# ArduinoUnoShield.net
KiCad netlist of a schematic drawn in Altium Designer
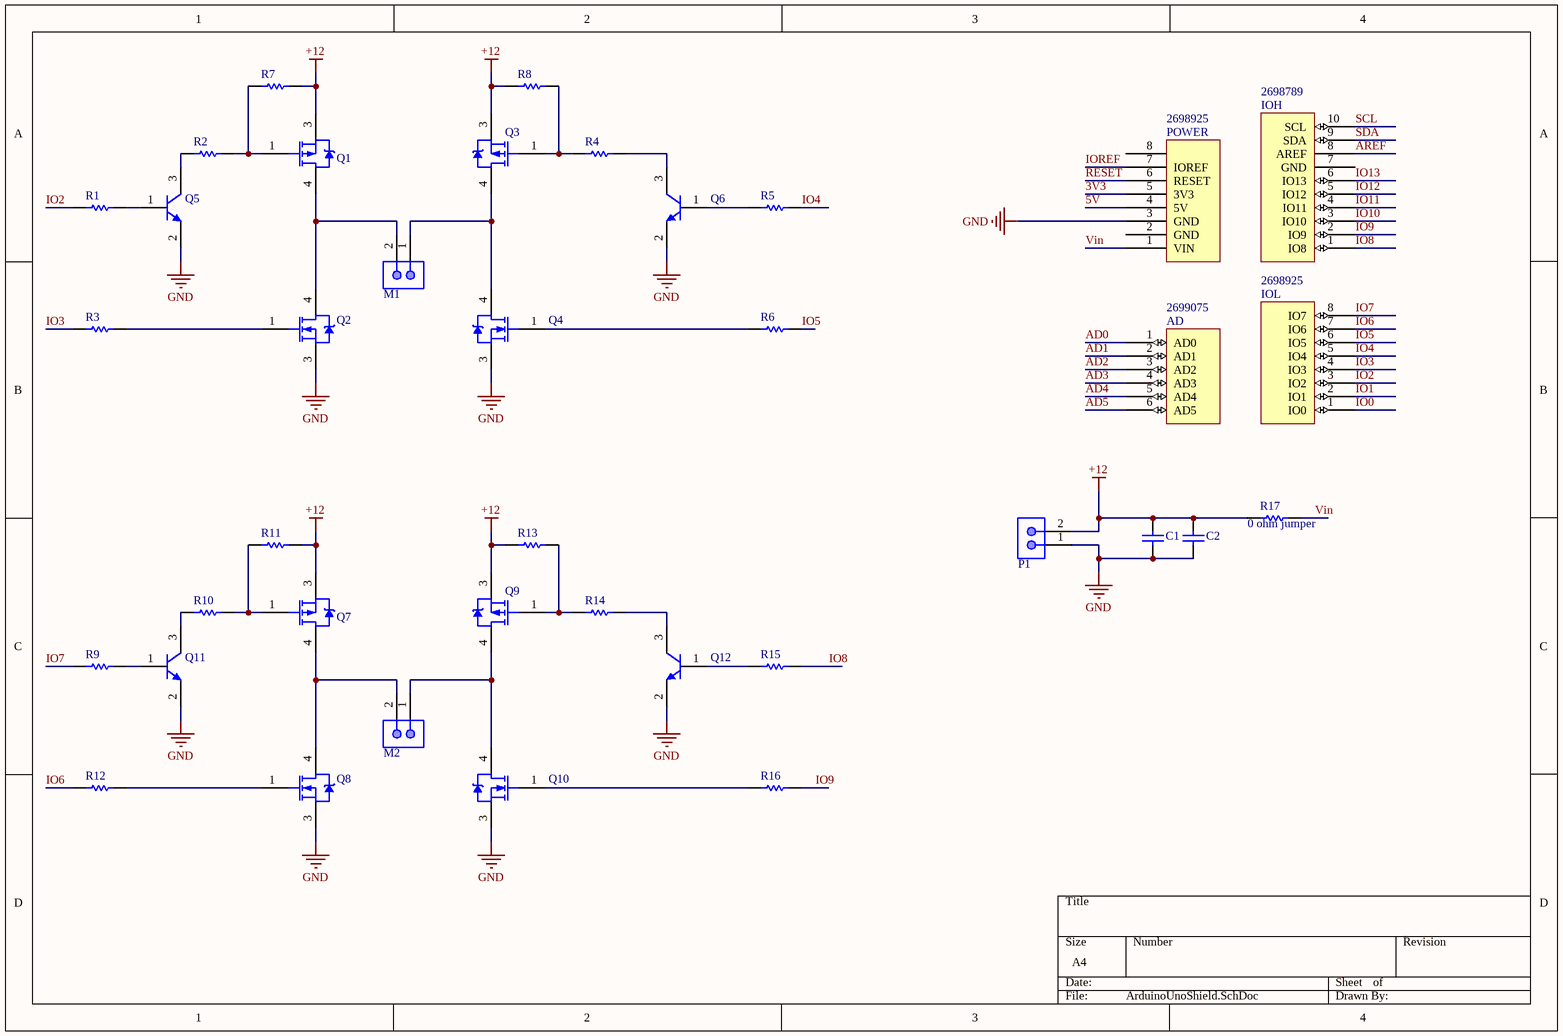
[diagram p0: ArduinoUnoShield.SchDoc]

(export (version "E")
  (design (tool "Eeschema 10.0.6"))
  (components
    (comp (ref "AD")
      (value "AD")
      (footprint "Header:Header 6x1 8.5mm")
      (fields (field (name "SUPPLIER PART NUMBER 4") "2699075"))
      (libsource (lib "Header") (part "AD"))
    )
    (comp (ref "C1")
      (value "CAP 100nF 50V 1206(3216)")
      (footprint "CAPC1206(3216)100_L")
      (description "CAP 100nF 50V ±10% 1206 (3216 Metric) Thickness 1mm SMD")
      (fields (field (name "TOLERANCE") "Â±10%"))
      (libsource (lib "Altium Content Vault") (part "CAP"))
    )
    (comp (ref "C2")
      (value "CAP 100nF 50V 1206(3216)")
      (footprint "CAPC1206(3216)100_L")
      (description "CAP 100nF 50V ±10% 1206 (3216 Metric) Thickness 1mm SMD")
      (fields (field (name "TOLERANCE") "Â±10%"))
      (libsource (lib "Altium Content Vault") (part "CAP"))
    )
    (comp (ref "IOH")
      (value "IOH")
      (footprint "Header:Header 10x1 8.5mm")
      (fields (field (name "SUPPLIER PART NUMBER 3") "2698789"))
      (libsource (lib "Header") (part "IOH"))
    )
    (comp (ref "IOL")
      (value "IOL")
      (footprint "Header 8x1 8.5mm")
      (fields (field (name "SUPPLIER PART NUMBER 4") "2698925"))
      (libsource (lib "Header") (part "IOL"))
    )
    (comp (ref "M1")
      (value "68000-102HLF")
      (footprint "AMPH-68000-102HLF_V")
      (description "Male Header, Pitch 2.54 mm, 1 x 2 Position, Height 8.38 mm, Tail Length 2.41 mm, RoHS, Bulk")
      (fields (field (name "MANUFACTURER") "FCI"))
      (libsource (lib "Altium Content Vault") (part "CN-1P-M-R2"))
    )
    (comp (ref "M2")
      (value "68000-102HLF")
      (footprint "AMPH-68000-102HLF_V")
      (description "Male Header, Pitch 2.54 mm, 1 x 2 Position, Height 8.38 mm, Tail Length 2.41 mm, RoHS, Bulk")
      (fields (field (name "MANUFACTURER") "FCI"))
      (libsource (lib "Altium Content Vault") (part "CN-1P-M-R2"))
    )
    (comp (ref "P1")
      (value "68000-102HLF")
      (footprint "AMPH-68000-102HLF_V")
      (description "Male Header, Pitch 2.54 mm, 1 x 2 Position, Height 8.38 mm, Tail Length 2.41 mm, RoHS, Bulk")
      (fields (field (name "MANUFACTURER") "FCI"))
      (libsource (lib "") (part "CN-1P-M-R2_1"))
    )
    (comp (ref "POWER")
      (value "POWER_UNO")
      (footprint "Header 8x1 8.5mm")
      (fields (field (name "SUPPLIER PART NUMBER 4") "2698925"))
      (libsource (lib "Header") (part "POWER_UNO"))
    )
    (comp (ref "Q1")
      (value "IRF9630STRLPBF‎")
      (footprint "ONSC-D2PAK-3-418B-04_V")
      (description "Power MOSFET, 50 A, 30 V, Logic Level, P-Channel, 3-Pin D2PAK, Pb-Free, Tape and Reel")
      (fields (field (name "PARTNUMBER") "MTB50P03HDLT4G") (field (name "MANUFACTURER") "On Semiconductor"))
      (libsource (lib "Altium Content Vault") (part "ONSC-PMOS-G1S3D4-3_B"))
    )
    (comp (ref "Q2")
      (value "IRF630NSTRLPBF‎")
      (footprint "ONSC-D2PAK-3-418B-04_V")
      (description "Power MOSFET, 60 V, 60 A, N-Channel, 3-Pin D2PAK, Pb-Free, Tape and Reel")
      (fields (field (name "MANUFACTURER") "On Semiconductor") (field (name "PARTNUMBER") "NTB60N06T4G"))
      (libsource (lib "Altium Content Vault") (part "ONSC-NMOS-G1S3D4-3_C"))
    )
    (comp (ref "Q3")
      (value "IRF9630STRLPBF‎")
      (footprint "ONSC-D2PAK-3-418B-04_V")
      (description "Power MOSFET, 50 A, 30 V, Logic Level, P-Channel, 3-Pin D2PAK, Pb-Free, Tape and Reel")
      (fields (field (name "PARTNUMBER") "MTB50P03HDLT4G") (field (name "MANUFACTURER") "On Semiconductor"))
      (libsource (lib "Altium Content Vault") (part "ONSC-PMOS-G1S3D4-3_B"))
    )
    (comp (ref "Q4")
      (value "IRF630NSTRLPBF‎")
      (footprint "ONSC-D2PAK-3-418B-04_V")
      (description "Power MOSFET, 60 V, 60 A, N-Channel, 3-Pin D2PAK, Pb-Free, Tape and Reel")
      (fields (field (name "MANUFACTURER") "On Semiconductor") (field (name "PARTNUMBER") "NTB60N06T4G"))
      (libsource (lib "Altium Content Vault") (part "ONSC-NMOS-G1S3D4-3_C"))
    )
    (comp (ref "Q5")
      (value "BC817-16LT1G")
      (footprint "ONSC-SOT-23-3-318-08_V")
      (description "General Purpose Transistor, NPN Silicon, 3-Pin SOT-23, Pb-Free, Tape and Reel")
      (fields (field (name "MANUFACTURER") "On Semiconductor"))
      (libsource (lib "Altium Content Vault") (part "ONSC-NPN-B1E2C3-3"))
    )
    (comp (ref "Q6")
      (value "BC817-16LT1G")
      (footprint "ONSC-SOT-23-3-318-08_V")
      (description "General Purpose Transistor, NPN Silicon, 3-Pin SOT-23, Pb-Free, Tape and Reel")
      (fields (field (name "MANUFACTURER") "On Semiconductor"))
      (libsource (lib "Altium Content Vault") (part "ONSC-NPN-B1E2C3-3"))
    )
    (comp (ref "Q7")
      (value "IRF9630STRLPBF‎")
      (footprint "ONSC-D2PAK-3-418B-04_V")
      (description "Power MOSFET, 50 A, 30 V, Logic Level, P-Channel, 3-Pin D2PAK, Pb-Free, Tape and Reel")
      (fields (field (name "PARTNUMBER") "MTB50P03HDLT4G") (field (name "MANUFACTURER") "On Semiconductor"))
      (libsource (lib "Altium Content Vault") (part "ONSC-PMOS-G1S3D4-3_B"))
    )
    (comp (ref "Q8")
      (value "IRF630NSTRLPBF‎")
      (footprint "ONSC-D2PAK-3-418B-04_V")
      (description "Power MOSFET, 60 V, 60 A, N-Channel, 3-Pin D2PAK, Pb-Free, Tape and Reel")
      (fields (field (name "MANUFACTURER") "On Semiconductor") (field (name "PARTNUMBER") "NTB60N06T4G"))
      (libsource (lib "Altium Content Vault") (part "ONSC-NMOS-G1S3D4-3_C"))
    )
    (comp (ref "Q9")
      (value "IRF9630STRLPBF‎")
      (footprint "ONSC-D2PAK-3-418B-04_V")
      (description "Power MOSFET, 50 A, 30 V, Logic Level, P-Channel, 3-Pin D2PAK, Pb-Free, Tape and Reel")
      (fields (field (name "PARTNUMBER") "MTB50P03HDLT4G") (field (name "MANUFACTURER") "On Semiconductor"))
      (libsource (lib "Altium Content Vault") (part "ONSC-PMOS-G1S3D4-3_B"))
    )
    (comp (ref "Q10")
      (value "IRF630NSTRLPBF‎")
      (footprint "ONSC-D2PAK-3-418B-04_V")
      (description "Power MOSFET, 60 V, 60 A, N-Channel, 3-Pin D2PAK, Pb-Free, Tape and Reel")
      (fields (field (name "MANUFACTURER") "On Semiconductor") (field (name "PARTNUMBER") "NTB60N06T4G"))
      (libsource (lib "Altium Content Vault") (part "ONSC-NMOS-G1S3D4-3_C"))
    )
    (comp (ref "Q11")
      (value "BC817-16LT1G")
      (footprint "ONSC-SOT-23-3-318-08_V")
      (description "General Purpose Transistor, NPN Silicon, 3-Pin SOT-23, Pb-Free, Tape and Reel")
      (fields (field (name "MANUFACTURER") "On Semiconductor"))
      (libsource (lib "Altium Content Vault") (part "ONSC-NPN-B1E2C3-3"))
    )
    (comp (ref "Q12")
      (value "BC817-16LT1G")
      (footprint "ONSC-SOT-23-3-318-08_V")
      (description "General Purpose Transistor, NPN Silicon, 3-Pin SOT-23, Pb-Free, Tape and Reel")
      (fields (field (name "MANUFACTURER") "On Semiconductor"))
      (libsource (lib "Altium Content Vault") (part "ONSC-NPN-B1E2C3-3"))
    )
    (comp (ref "R1")
      (value "CRCW1206220KFKEA")
      (footprint "RESC3216X60X45NL10T20")
      (fields (field (name "MANUFACTURER") "Vishay Dale"))
      (libsource (lib "Altium Content Vault") (part "RES"))
    )
    (comp (ref "R2")
      (value "CRCW1206220KFKEA")
      (footprint "RESC3216X60X45NL10T20")
      (fields (field (name "MANUFACTURER") "Vishay Dale"))
      (libsource (lib "Altium Content Vault") (part "RES"))
    )
    (comp (ref "R3")
      (value "CRCW1206220KFKEA")
      (footprint "RESC3216X60X45NL10T20")
      (fields (field (name "MANUFACTURER") "Vishay Dale"))
      (libsource (lib "Altium Content Vault") (part "RES"))
    )
    (comp (ref "R4")
      (value "CRCW1206220KFKEA")
      (footprint "RESC3216X60X45NL10T20")
      (fields (field (name "MANUFACTURER") "Vishay Dale"))
      (libsource (lib "Altium Content Vault") (part "RES"))
    )
    (comp (ref "R5")
      (value "CRCW1206220KFKEA")
      (footprint "RESC3216X60X45NL10T20")
      (fields (field (name "MANUFACTURER") "Vishay Dale"))
      (libsource (lib "Altium Content Vault") (part "RES"))
    )
    (comp (ref "R6")
      (value "CRCW1206220KFKEA")
      (footprint "RESC3216X60X45NL10T20")
      (fields (field (name "MANUFACTURER") "Vishay Dale"))
      (libsource (lib "Altium Content Vault") (part "RES"))
    )
    (comp (ref "R7")
      (value "CRCW1206220KFKEA")
      (footprint "RESC3216X60X45NL10T20")
      (fields (field (name "MANUFACTURER") "Vishay Dale"))
      (libsource (lib "Altium Content Vault") (part "RES"))
    )
    (comp (ref "R8")
      (value "CRCW1206220KFKEA")
      (footprint "RESC3216X60X45NL10T20")
      (fields (field (name "MANUFACTURER") "Vishay Dale"))
      (libsource (lib "Altium Content Vault") (part "RES"))
    )
    (comp (ref "R9")
      (value "CRCW1206220KFKEA")
      (footprint "RESC3216X60X45NL10T20")
      (fields (field (name "MANUFACTURER") "Vishay Dale"))
      (libsource (lib "Altium Content Vault") (part "RES"))
    )
    (comp (ref "R10")
      (value "CRCW1206220KFKEA")
      (footprint "RESC3216X60X45NL10T20")
      (fields (field (name "MANUFACTURER") "Vishay Dale"))
      (libsource (lib "Altium Content Vault") (part "RES"))
    )
    (comp (ref "R11")
      (value "CRCW1206220KFKEA")
      (footprint "RESC3216X60X45NL10T20")
      (fields (field (name "MANUFACTURER") "Vishay Dale"))
      (libsource (lib "Altium Content Vault") (part "RES"))
    )
    (comp (ref "R12")
      (value "CRCW1206220KFKEA")
      (footprint "RESC3216X60X45NL10T20")
      (fields (field (name "MANUFACTURER") "Vishay Dale"))
      (libsource (lib "Altium Content Vault") (part "RES"))
    )
    (comp (ref "R13")
      (value "CRCW1206220KFKEA")
      (footprint "RESC3216X60X45NL10T20")
      (fields (field (name "MANUFACTURER") "Vishay Dale"))
      (libsource (lib "Altium Content Vault") (part "RES"))
    )
    (comp (ref "R14")
      (value "CRCW1206220KFKEA")
      (footprint "RESC3216X60X45NL10T20")
      (fields (field (name "MANUFACTURER") "Vishay Dale"))
      (libsource (lib "Altium Content Vault") (part "RES"))
    )
    (comp (ref "R15")
      (value "CRCW1206220KFKEA")
      (footprint "RESC3216X60X45NL10T20")
      (fields (field (name "MANUFACTURER") "Vishay Dale"))
      (libsource (lib "Altium Content Vault") (part "RES"))
    )
    (comp (ref "R16")
      (value "CRCW1206220KFKEA")
      (footprint "RESC3216X60X45NL10T20")
      (fields (field (name "MANUFACTURER") "Vishay Dale"))
      (libsource (lib "Altium Content Vault") (part "RES"))
    )
    (comp (ref "R17")
      (value "CRCW1206220KFKEA")
      (footprint "RESC3216X60X45NL10T20")
      (fields (field (name "MANUFACTURER") "Vishay Dale"))
      (libsource (lib "Altium Content Vault") (part "RES"))
    )
  )
  (nets
    (net (code "1") (name "+12") (class "Default")
      (node (ref "C1") (pin "1") (pinfunction "1_1") (pintype "passive"))
      (node (ref "C2") (pin "1") (pinfunction "1_1") (pintype "passive"))
      (node (ref "P1") (pin "2") (pinfunction "2_2") (pintype "passive"))
      (node (ref "Q1") (pin "3") (pinfunction "S_3") (pintype "passive"))
      (node (ref "Q3") (pin "3") (pinfunction "S_3") (pintype "passive"))
      (node (ref "Q7") (pin "3") (pinfunction "S_3") (pintype "passive"))
      (node (ref "Q9") (pin "3") (pinfunction "S_3") (pintype "passive"))
      (node (ref "R11") (pin "2") (pinfunction "2_2") (pintype "passive"))
      (node (ref "R13") (pin "1") (pinfunction "1_1") (pintype "passive"))
      (node (ref "R17") (pin "1") (pinfunction "1_1") (pintype "passive"))
      (node (ref "R7") (pin "2") (pinfunction "2_2") (pintype "passive"))
      (node (ref "R8") (pin "1") (pinfunction "1_1") (pintype "passive"))
    )
    (net (code "2") (name "/3V3") (class "Default")
      (node (ref "POWER") (pin "5") (pinfunction "3V3_5") (pintype "power_in"))
    )
    (net (code "3") (name "/5V") (class "Default")
      (node (ref "POWER") (pin "4") (pinfunction "5V_4") (pintype "power_in"))
    )
    (net (code "5") (name "/AD0") (class "Default")
      (node (ref "AD") (pin "1") (pinfunction "AD0_1") (pintype "bidirectional"))
    )
    (net (code "6") (name "/AD1") (class "Default")
      (node (ref "AD") (pin "2") (pinfunction "AD1_2") (pintype "bidirectional"))
    )
    (net (code "7") (name "/AD2") (class "Default")
      (node (ref "AD") (pin "3") (pinfunction "AD2_3") (pintype "bidirectional"))
    )
    (net (code "8") (name "/AD3") (class "Default")
      (node (ref "AD") (pin "4") (pinfunction "AD3_4") (pintype "bidirectional"))
    )
    (net (code "9") (name "/AD4") (class "Default")
      (node (ref "AD") (pin "5") (pinfunction "AD4_5") (pintype "bidirectional"))
    )
    (net (code "10") (name "/AD5") (class "Default")
      (node (ref "AD") (pin "6") (pinfunction "AD5_6") (pintype "bidirectional"))
    )
    (net (code "11") (name "/AREF") (class "Default")
      (node (ref "IOH") (pin "8") (pinfunction "AREF_8") (pintype "passive"))
    )
    (net (code "12") (name "/IO0") (class "Default")
      (node (ref "IOL") (pin "1") (pinfunction "IO0_1") (pintype "bidirectional"))
    )
    (net (code "13") (name "/IO1") (class "Default")
      (node (ref "IOL") (pin "2") (pinfunction "IO1_2") (pintype "bidirectional"))
    )
    (net (code "14") (name "/IO2") (class "Default")
      (node (ref "IOL") (pin "3") (pinfunction "IO2_3") (pintype "bidirectional"))
      (node (ref "R1") (pin "1") (pinfunction "1_1") (pintype "passive"))
    )
    (net (code "15") (name "/IO3") (class "Default")
      (node (ref "IOL") (pin "4") (pinfunction "IO3_4") (pintype "bidirectional"))
      (node (ref "R3") (pin "1") (pinfunction "1_1") (pintype "passive"))
    )
    (net (code "16") (name "/IO4") (class "Default")
      (node (ref "IOL") (pin "5") (pinfunction "IO4_5") (pintype "bidirectional"))
      (node (ref "R5") (pin "2") (pinfunction "2_2") (pintype "passive"))
    )
    (net (code "17") (name "/IO5") (class "Default")
      (node (ref "IOL") (pin "6") (pinfunction "IO5_6") (pintype "bidirectional"))
      (node (ref "R6") (pin "2") (pinfunction "2_2") (pintype "passive"))
    )
    (net (code "18") (name "/IO6") (class "Default")
      (node (ref "IOL") (pin "7") (pinfunction "IO6_7") (pintype "bidirectional"))
      (node (ref "R12") (pin "1") (pinfunction "1_1") (pintype "passive"))
    )
    (net (code "19") (name "/IO7") (class "Default")
      (node (ref "IOL") (pin "8") (pinfunction "IO7_8") (pintype "bidirectional"))
      (node (ref "R9") (pin "1") (pinfunction "1_1") (pintype "passive"))
    )
    (net (code "20") (name "/IO8") (class "Default")
      (node (ref "IOH") (pin "1") (pinfunction "IO8_1") (pintype "bidirectional"))
      (node (ref "R15") (pin "2") (pinfunction "2_2") (pintype "passive"))
    )
    (net (code "21") (name "/IO9") (class "Default")
      (node (ref "IOH") (pin "2") (pinfunction "IO9_2") (pintype "bidirectional"))
      (node (ref "R16") (pin "2") (pinfunction "2_2") (pintype "passive"))
    )
    (net (code "22") (name "/IO10") (class "Default")
      (node (ref "IOH") (pin "3") (pinfunction "IO10_3") (pintype "bidirectional"))
    )
    (net (code "23") (name "/IO11") (class "Default")
      (node (ref "IOH") (pin "4") (pinfunction "IO11_4") (pintype "bidirectional"))
    )
    (net (code "24") (name "/IO12") (class "Default")
      (node (ref "IOH") (pin "5") (pinfunction "IO12_5") (pintype "bidirectional"))
    )
    (net (code "25") (name "/IO13") (class "Default")
      (node (ref "IOH") (pin "6") (pinfunction "IO13_6") (pintype "bidirectional"))
    )
    (net (code "26") (name "/IOREF") (class "Default")
      (node (ref "POWER") (pin "7") (pinfunction "IOREF_7") (pintype "power_in"))
    )
    (net (code "27") (name "/RESET") (class "Default")
      (node (ref "POWER") (pin "6") (pinfunction "RESET_6") (pintype "passive"))
    )
    (net (code "28") (name "/SCL") (class "Default")
      (node (ref "IOH") (pin "10") (pinfunction "SCL_10") (pintype "bidirectional"))
    )
    (net (code "29") (name "/SDA") (class "Default")
      (node (ref "IOH") (pin "9") (pinfunction "SDA_9") (pintype "bidirectional"))
    )
    (net (code "30") (name "/Vin") (class "Default")
      (node (ref "POWER") (pin "1") (pinfunction "VIN_1") (pintype "power_in"))
      (node (ref "R17") (pin "2") (pinfunction "2_2") (pintype "passive"))
    )
    (net (code "31") (name "GND") (class "Default")
      (node (ref "C1") (pin "2") (pinfunction "2_2") (pintype "passive"))
      (node (ref "C2") (pin "2") (pinfunction "2_2") (pintype "passive"))
      (node (ref "P1") (pin "1") (pinfunction "1_1") (pintype "passive"))
      (node (ref "POWER") (pin "3") (pinfunction "GND_3") (pintype "power_in"))
      (node (ref "Q10") (pin "3") (pinfunction "S_3") (pintype "passive"))
      (node (ref "Q11") (pin "2") (pinfunction "E_2") (pintype "passive"))
      (node (ref "Q12") (pin "2") (pinfunction "E_2") (pintype "passive"))
      (node (ref "Q2") (pin "3") (pinfunction "S_3") (pintype "passive"))
      (node (ref "Q4") (pin "3") (pinfunction "S_3") (pintype "passive"))
      (node (ref "Q5") (pin "2") (pinfunction "E_2") (pintype "passive"))
      (node (ref "Q6") (pin "2") (pinfunction "E_2") (pintype "passive"))
      (node (ref "Q8") (pin "3") (pinfunction "S_3") (pintype "passive"))
    )
    (net (code "32") (name "Net-(Q1-D)") (class "Default")
      (node (ref "M1") (pin "2") (pinfunction "2_2") (pintype "passive"))
      (node (ref "Q1") (pin "4") (pinfunction "D_4") (pintype "passive"))
      (node (ref "Q2") (pin "4") (pinfunction "D_4") (pintype "passive"))
    )
    (net (code "33") (name "Net-(Q1-G)") (class "Default")
      (node (ref "Q1") (pin "1") (pinfunction "G_1") (pintype "passive"))
      (node (ref "R2") (pin "2") (pinfunction "2_2") (pintype "passive"))
      (node (ref "R7") (pin "1") (pinfunction "1_1") (pintype "passive"))
    )
    (net (code "34") (name "Net-(Q2-G)") (class "Default")
      (node (ref "Q2") (pin "1") (pinfunction "G_1") (pintype "passive"))
      (node (ref "R3") (pin "2") (pinfunction "2_2") (pintype "passive"))
    )
    (net (code "35") (name "Net-(Q3-D)") (class "Default")
      (node (ref "M1") (pin "1") (pinfunction "1_1") (pintype "passive"))
      (node (ref "Q3") (pin "4") (pinfunction "D_4") (pintype "passive"))
      (node (ref "Q4") (pin "4") (pinfunction "D_4") (pintype "passive"))
    )
    (net (code "36") (name "Net-(Q3-G)") (class "Default")
      (node (ref "Q3") (pin "1") (pinfunction "G_1") (pintype "passive"))
      (node (ref "R4") (pin "1") (pinfunction "1_1") (pintype "passive"))
      (node (ref "R8") (pin "2") (pinfunction "2_2") (pintype "passive"))
    )
    (net (code "37") (name "Net-(Q4-G)") (class "Default")
      (node (ref "Q4") (pin "1") (pinfunction "G_1") (pintype "passive"))
      (node (ref "R6") (pin "1") (pinfunction "1_1") (pintype "passive"))
    )
    (net (code "38") (name "Net-(Q5-B)") (class "Default")
      (node (ref "Q5") (pin "1") (pinfunction "B_1") (pintype "passive"))
      (node (ref "R1") (pin "2") (pinfunction "2_2") (pintype "passive"))
    )
    (net (code "39") (name "Net-(Q5-C)") (class "Default")
      (node (ref "Q5") (pin "3") (pinfunction "C_3") (pintype "passive"))
      (node (ref "R2") (pin "1") (pinfunction "1_1") (pintype "passive"))
    )
    (net (code "40") (name "Net-(Q6-B)") (class "Default")
      (node (ref "Q6") (pin "1") (pinfunction "B_1") (pintype "passive"))
      (node (ref "R5") (pin "1") (pinfunction "1_1") (pintype "passive"))
    )
    (net (code "41") (name "Net-(Q6-C)") (class "Default")
      (node (ref "Q6") (pin "3") (pinfunction "C_3") (pintype "passive"))
      (node (ref "R4") (pin "2") (pinfunction "2_2") (pintype "passive"))
    )
    (net (code "42") (name "Net-(Q7-D)") (class "Default")
      (node (ref "M2") (pin "2") (pinfunction "2_2") (pintype "passive"))
      (node (ref "Q7") (pin "4") (pinfunction "D_4") (pintype "passive"))
      (node (ref "Q8") (pin "4") (pinfunction "D_4") (pintype "passive"))
    )
    (net (code "43") (name "Net-(Q7-G)") (class "Default")
      (node (ref "Q7") (pin "1") (pinfunction "G_1") (pintype "passive"))
      (node (ref "R10") (pin "2") (pinfunction "2_2") (pintype "passive"))
      (node (ref "R11") (pin "1") (pinfunction "1_1") (pintype "passive"))
    )
    (net (code "44") (name "Net-(Q8-G)") (class "Default")
      (node (ref "Q8") (pin "1") (pinfunction "G_1") (pintype "passive"))
      (node (ref "R12") (pin "2") (pinfunction "2_2") (pintype "passive"))
    )
    (net (code "45") (name "Net-(Q9-G)") (class "Default")
      (node (ref "Q9") (pin "1") (pinfunction "G_1") (pintype "passive"))
      (node (ref "R13") (pin "2") (pinfunction "2_2") (pintype "passive"))
      (node (ref "R14") (pin "1") (pinfunction "1_1") (pintype "passive"))
    )
    (net (code "46") (name "Net-(Q10-D)") (class "Default")
      (node (ref "M2") (pin "1") (pinfunction "1_1") (pintype "passive"))
      (node (ref "Q10") (pin "4") (pinfunction "D_4") (pintype "passive"))
      (node (ref "Q9") (pin "4") (pinfunction "D_4") (pintype "passive"))
    )
    (net (code "47") (name "Net-(Q10-G)") (class "Default")
      (node (ref "Q10") (pin "1") (pinfunction "G_1") (pintype "passive"))
      (node (ref "R16") (pin "1") (pinfunction "1_1") (pintype "passive"))
    )
    (net (code "48") (name "Net-(Q11-B)") (class "Default")
      (node (ref "Q11") (pin "1") (pinfunction "B_1") (pintype "passive"))
      (node (ref "R9") (pin "2") (pinfunction "2_2") (pintype "passive"))
    )
    (net (code "49") (name "Net-(Q11-C)") (class "Default")
      (node (ref "Q11") (pin "3") (pinfunction "C_3") (pintype "passive"))
      (node (ref "R10") (pin "1") (pinfunction "1_1") (pintype "passive"))
    )
    (net (code "50") (name "Net-(Q12-B)") (class "Default")
      (node (ref "Q12") (pin "1") (pinfunction "B_1") (pintype "passive"))
      (node (ref "R15") (pin "1") (pinfunction "1_1") (pintype "passive"))
    )
    (net (code "51") (name "Net-(Q12-C)") (class "Default")
      (node (ref "Q12") (pin "3") (pinfunction "C_3") (pintype "passive"))
      (node (ref "R14") (pin "2") (pinfunction "2_2") (pintype "passive"))
    )
    (net (code "52") (name "unconnected-(IOH-GND-Pad7)") (class "Default")
      (node (ref "IOH") (pin "7") (pinfunction "GND_7") (pintype "power_in"))
    )
    (net (code "53") (name "unconnected-(POWER-GND-Pad2)") (class "Default")
      (node (ref "POWER") (pin "2") (pinfunction "GND_2") (pintype "power_in"))
    )
    (net (code "54") (name "unconnected-(POWER-Pad8)") (class "Default")
      (node (ref "POWER") (pin "8") (pintype "passive"))
    )
  )
)
